# Main.net
KiCad netlist of a schematic drawn in Altium Designer
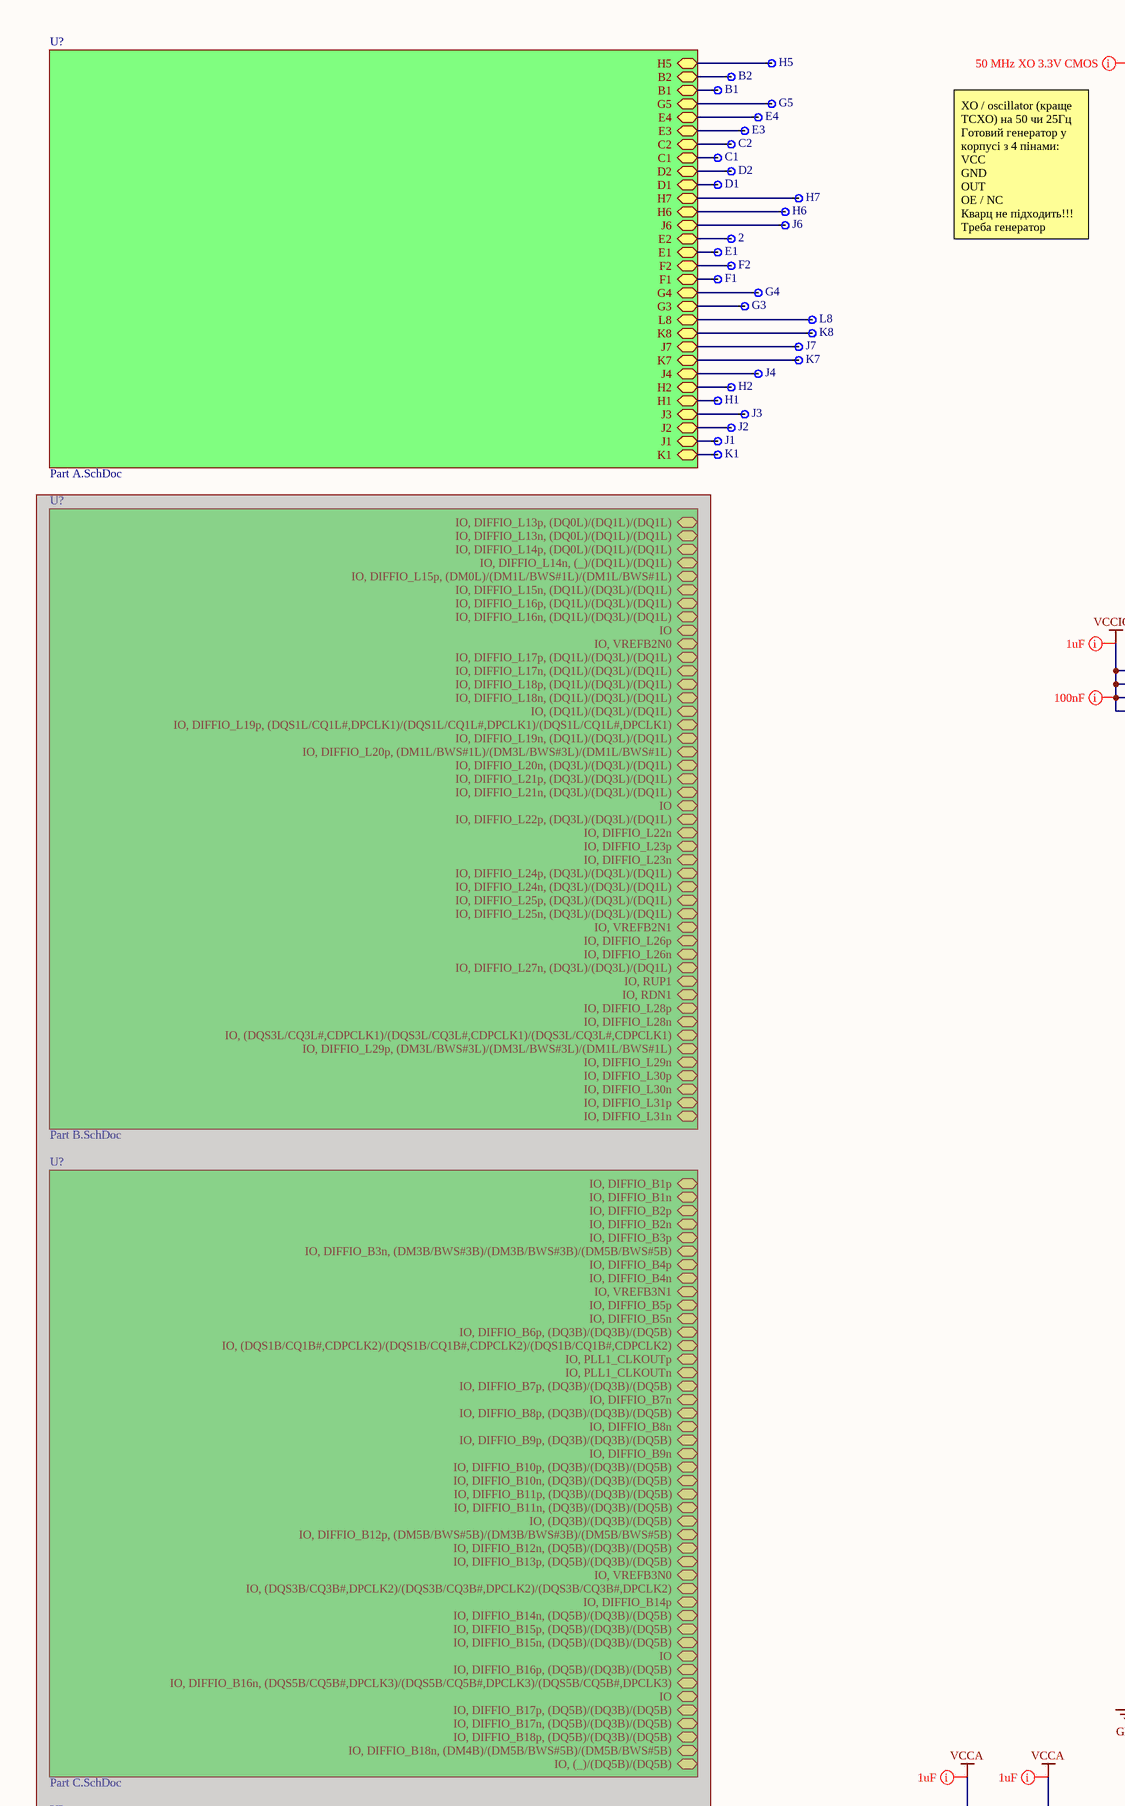
[diagram p0: Main.SchDoc, top left]
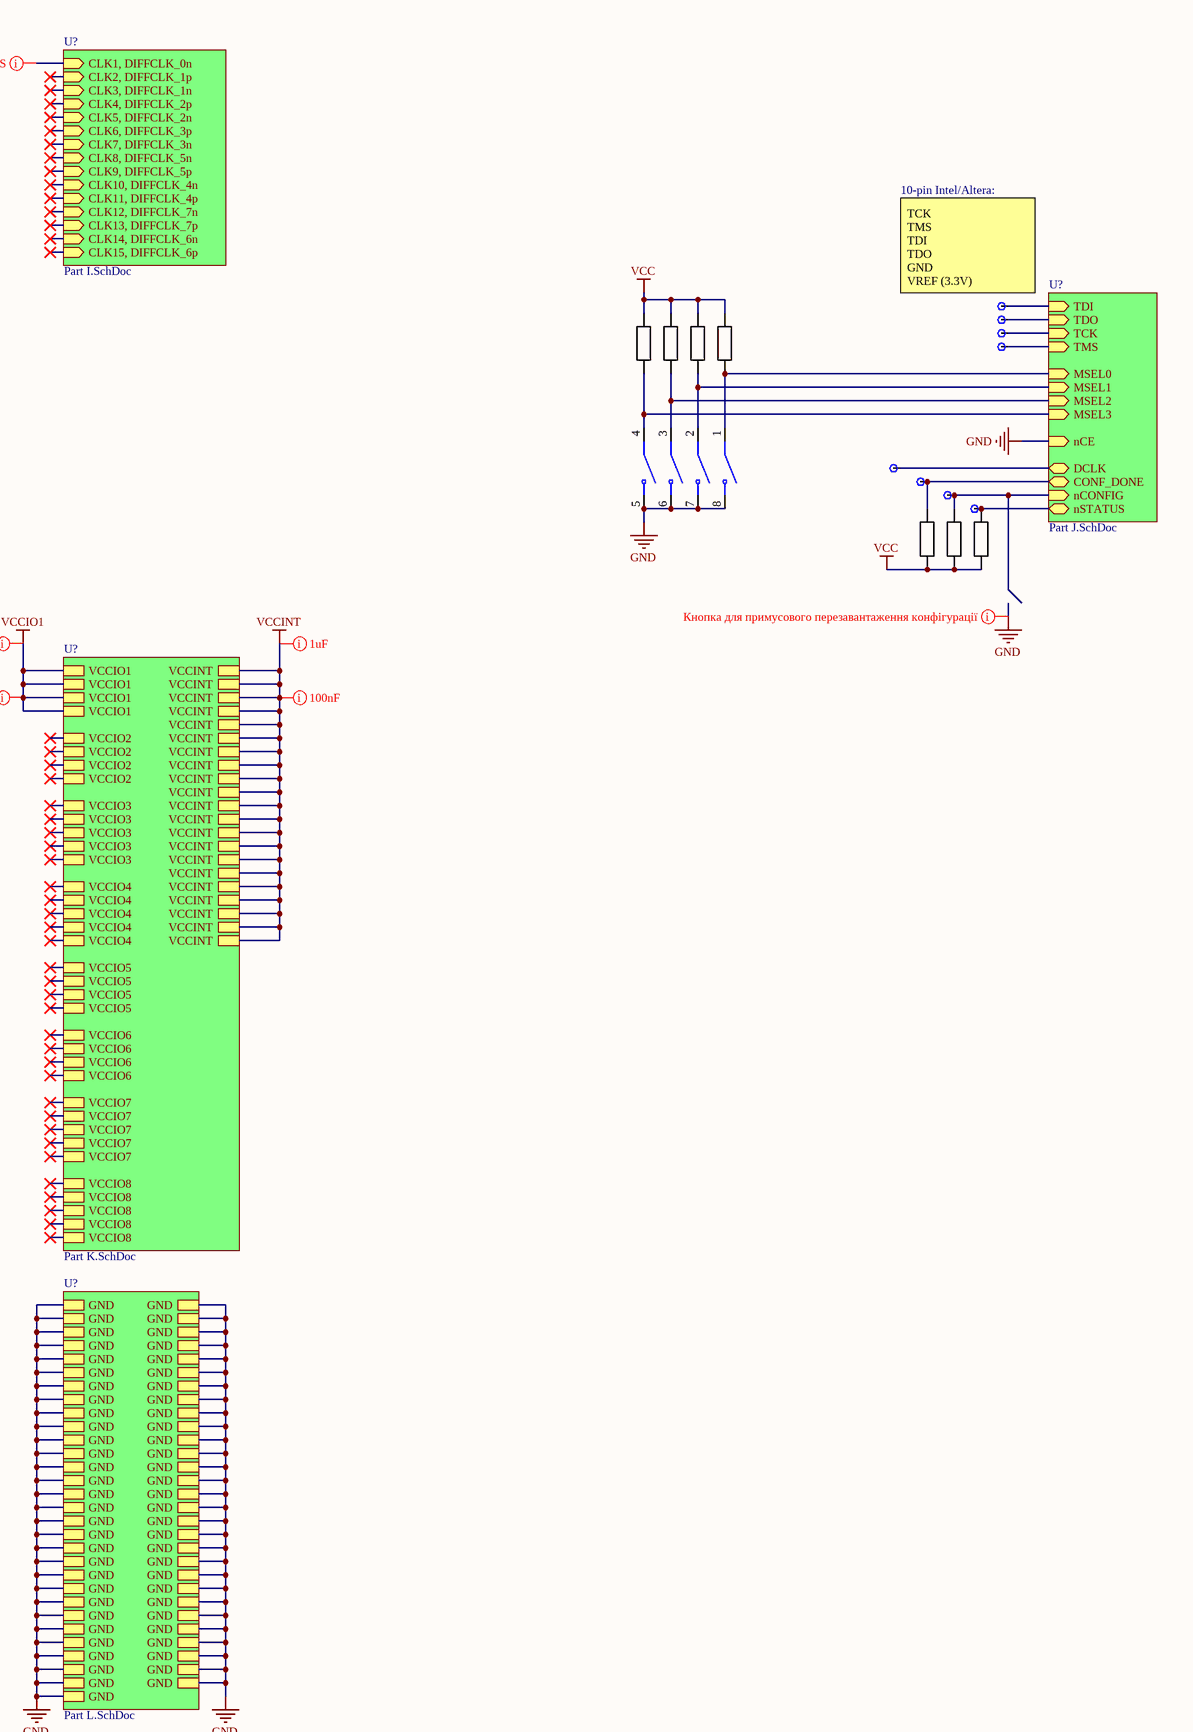
[diagram p1: Main.SchDoc, top right]
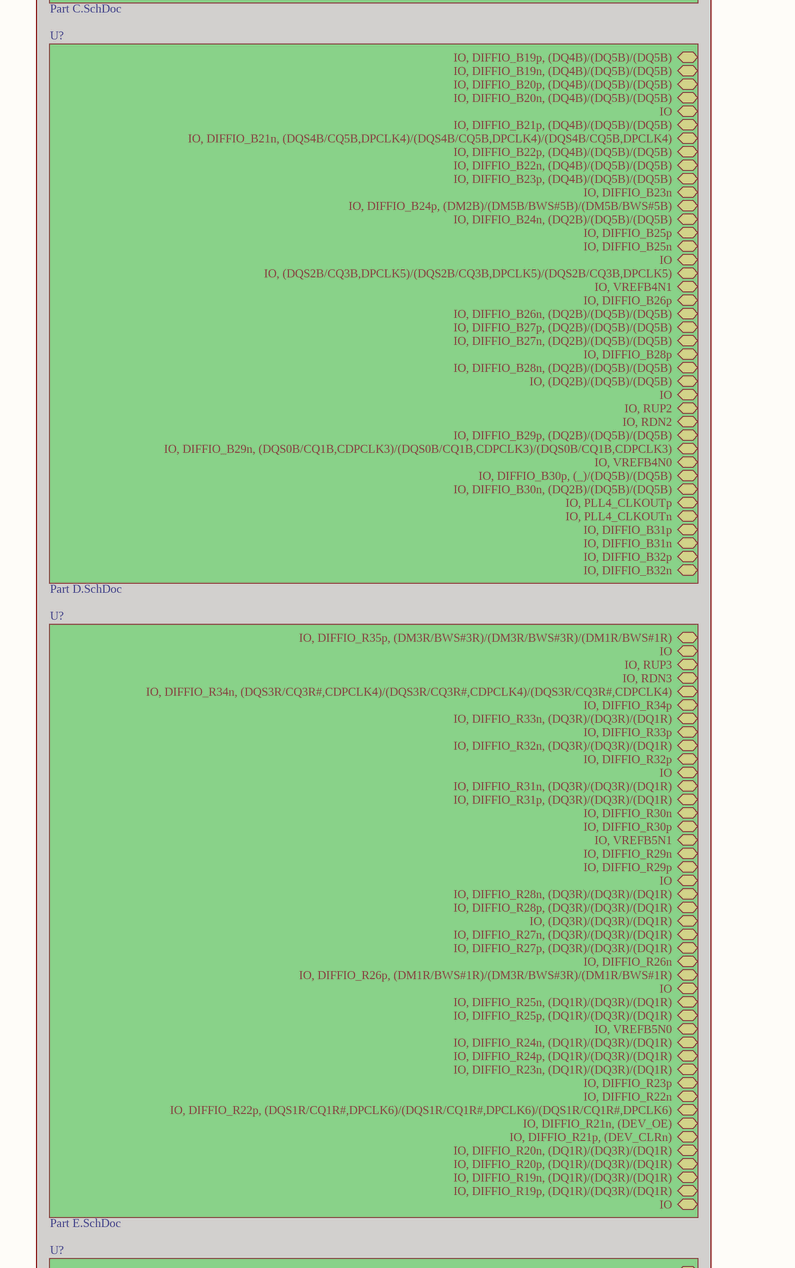
[diagram p2: Main.SchDoc, centre left]
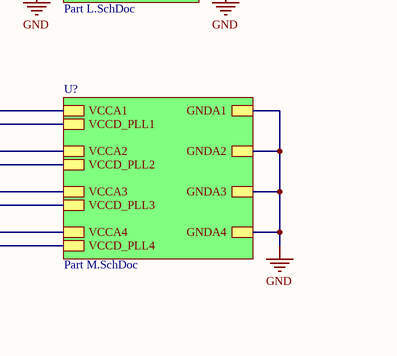
[diagram p3: Main.SchDoc, centre right]
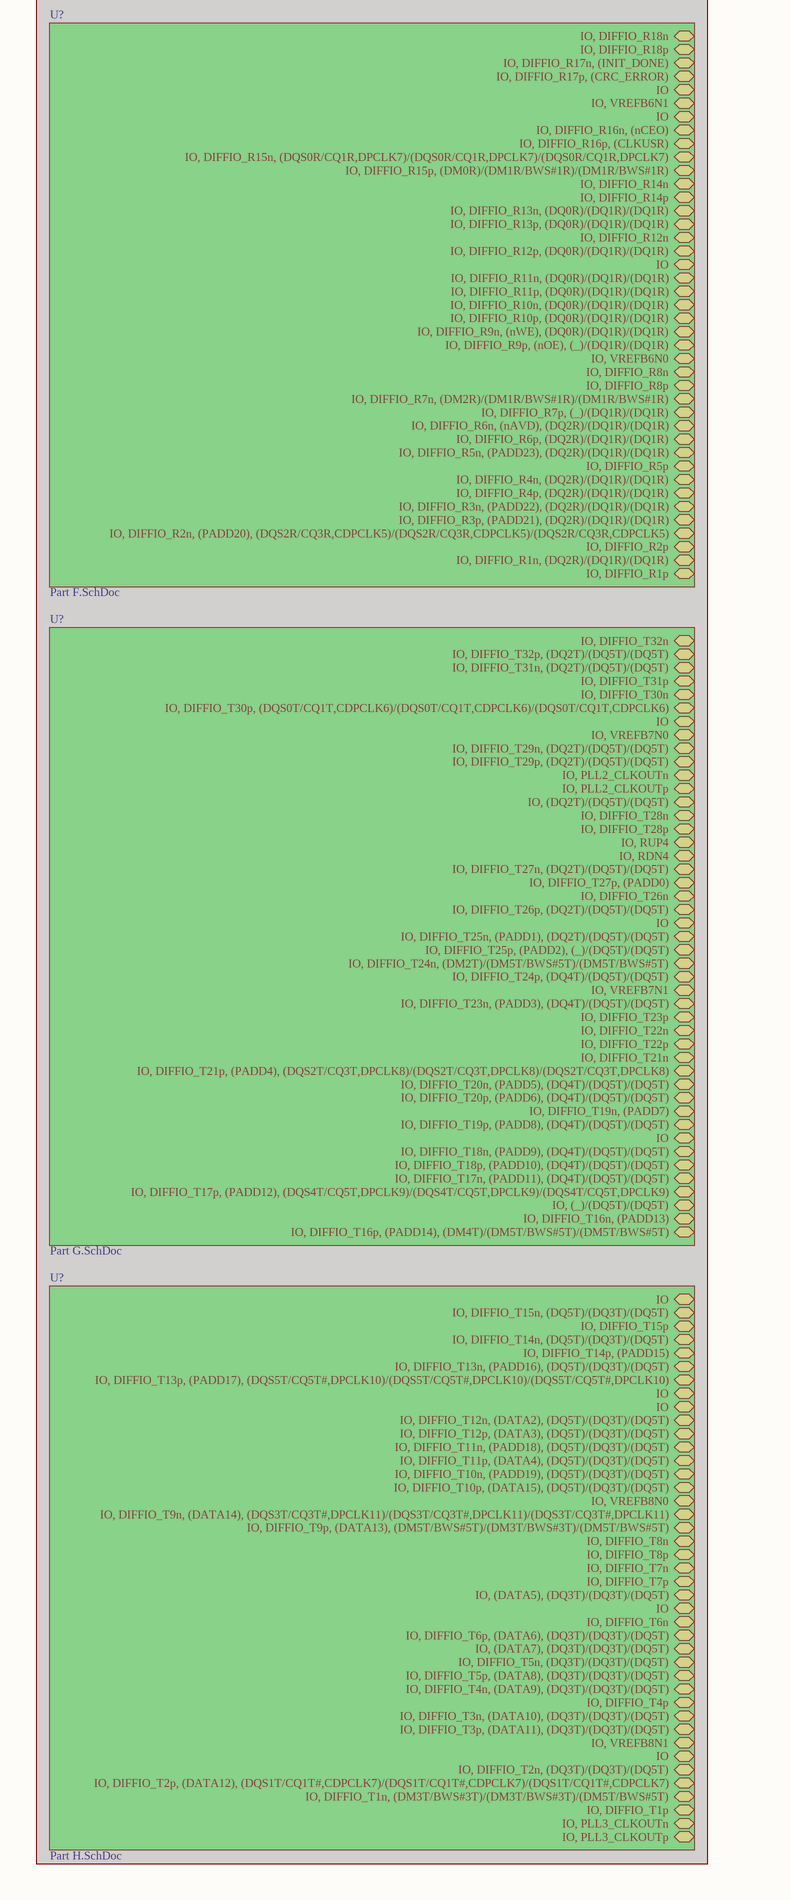
[diagram p4: Main.SchDoc, bottom left]

(export (version "E")
  (design (tool "Eeschema 10.0.6"))
  (components
    (comp (ref "J161") (value "H5") (footprint "Pin1") (libsource (lib "Schlib1") (part "Pin1")))
    (comp (ref "J162") (value "B2") (footprint "Pin1") (libsource (lib "Schlib1") (part "Pin1")))
    (comp (ref "J163") (value "B1") (footprint "Pin1") (libsource (lib "Schlib1") (part "Pin1")))
    (comp (ref "J164") (value "G5") (footprint "Pin1") (libsource (lib "Schlib1") (part "Pin1")))
    (comp (ref "J165") (value "E4") (footprint "Pin1") (libsource (lib "Schlib1") (part "Pin1")))
    (comp (ref "J166") (value "E3") (footprint "Pin1") (libsource (lib "Schlib1") (part "Pin1")))
    (comp (ref "J167") (value "C2") (footprint "Pin1") (libsource (lib "Schlib1") (part "Pin1")))
    (comp (ref "J168") (value "C1") (footprint "Pin1") (libsource (lib "Schlib1") (part "Pin1")))
    (comp (ref "J169") (value "D2") (footprint "Pin1") (libsource (lib "Schlib1") (part "Pin1")))
    (comp (ref "J170") (value "D1") (footprint "Pin1") (libsource (lib "Schlib1") (part "Pin1")))
    (comp (ref "J171") (value "H7") (footprint "Pin1") (libsource (lib "Schlib1") (part "Pin1")))
    (comp (ref "J172") (value "H6") (footprint "Pin1") (libsource (lib "Schlib1") (part "Pin1")))
    (comp (ref "J173") (value "J6") (footprint "Pin1") (libsource (lib "Schlib1") (part "Pin1")))
    (comp (ref "J174") (value "2") (footprint "Pin1") (libsource (lib "Schlib1") (part "Pin1")))
    (comp (ref "J175") (value "E1") (footprint "Pin1") (libsource (lib "Schlib1") (part "Pin1")))
    (comp (ref "J176") (value "F2") (footprint "Pin1") (libsource (lib "Schlib1") (part "Pin1")))
    (comp (ref "J177") (value "F1") (footprint "Pin1") (libsource (lib "Schlib1") (part "Pin1")))
    (comp (ref "J178") (value "G4") (footprint "Pin1") (libsource (lib "Schlib1") (part "Pin1")))
    (comp (ref "J179") (value "G3") (footprint "Pin1") (libsource (lib "Schlib1") (part "Pin1")))
    (comp (ref "J180") (value "Pin1") (footprint "Pin1") (libsource (lib "Schlib1") (part "Pin1")))
    (comp (ref "J181") (value "L8") (footprint "Pin1") (libsource (lib "Schlib1") (part "Pin1")))
    (comp (ref "J182") (value "Pin1") (footprint "Pin1") (libsource (lib "Schlib1") (part "Pin1")))
    (comp (ref "J183") (value "K8") (footprint "Pin1") (libsource (lib "Schlib1") (part "Pin1")))
    (comp (ref "J184") (value "Pin1") (footprint "Pin1") (libsource (lib "Schlib1") (part "Pin1")))
    (comp (ref "J185") (value "J7") (footprint "Pin1") (libsource (lib "Schlib1") (part "Pin1")))
    (comp (ref "J186") (value "Pin1") (footprint "Pin1") (libsource (lib "Schlib1") (part "Pin1")))
    (comp (ref "J187") (value "K7") (footprint "Pin1") (libsource (lib "Schlib1") (part "Pin1")))
    (comp (ref "J188") (value "J4") (footprint "Pin1") (libsource (lib "Schlib1") (part "Pin1")))
    (comp (ref "J189") (value "H2") (footprint "Pin1") (libsource (lib "Schlib1") (part "Pin1")))
    (comp (ref "J190") (value "H1") (footprint "Pin1") (libsource (lib "Schlib1") (part "Pin1")))
    (comp (ref "J191") (value "J3") (footprint "Pin1") (libsource (lib "Schlib1") (part "Pin1")))
    (comp (ref "J192") (value "J2") (footprint "Pin1") (libsource (lib "Schlib1") (part "Pin1")))
    (comp (ref "J193") (value "J1") (footprint "Pin1") (libsource (lib "Schlib1") (part "Pin1")))
    (comp (ref "J194") (value "K1") (footprint "Pin1") (libsource (lib "Schlib1") (part "Pin1")))
    (comp (ref "J195") (value "Pin1") (footprint "Pin1") (libsource (lib "Schlib1") (part "Pin1")))
    (comp (ref "J196") (value "Pin1") (footprint "Pin1") (libsource (lib "Schlib1") (part "Pin1")))
    (comp (ref "J197") (value "Pin1") (footprint "Pin1") (libsource (lib "Schlib1") (part "Pin1")))
    (comp (ref "J198") (value "Pin1") (footprint "Pin1") (libsource (lib "Schlib1") (part "Pin1")))
    (comp (ref "R1")
      (value "10kOm 0603")
      (footprint "RES 0603")
      (libsource (lib "Schlib1") (part "10kOm 0603"))
    )
    (comp (ref "R2")
      (value "10kOm 0603")
      (footprint "RES 0603")
      (libsource (lib "Schlib1") (part "10kOm 0603"))
    )
    (comp (ref "R3")
      (value "10kOm 0603")
      (footprint "RES 0603")
      (libsource (lib "Schlib1") (part "10kOm 0603"))
    )
    (comp (ref "R4")
      (value "10kOm 0603")
      (footprint "RES 0603")
      (libsource (lib "Schlib1") (part "10kOm 0603"))
    )
    (comp (ref "R5")
      (value "10kOm 0603")
      (footprint "RES 0603")
      (libsource (lib "Schlib1") (part "10kOm 0603"))
    )
    (comp (ref "R6")
      (value "10kOm 0603")
      (footprint "RES 0603")
      (libsource (lib "Schlib1") (part "10kOm 0603"))
    )
    (comp (ref "R7")
      (value "10kOm 0603")
      (footprint "RES 0603")
      (libsource (lib "Schlib1") (part "10kOm 0603"))
    )
    (comp (ref "S1")
      (value "206-4")
      (footprint "SW_206-4")
      (fields (field (name "MF") "{'manufacturer': u'CTS Components'}"))
      (libsource (lib "Schlib1") (part "206-4"))
    )
  )
  (nets
    (net (code "1") (name "/B1") (class "Default")
      (node (ref "J163") (pin "1") (pinfunction "1_1") (pintype "passive"))
    )
    (net (code "2") (name "/B2") (class "Default")
      (node (ref "J162") (pin "1") (pinfunction "1_1") (pintype "passive"))
    )
    (net (code "3") (name "/C1") (class "Default")
      (node (ref "J168") (pin "1") (pinfunction "1_1") (pintype "passive"))
    )
    (net (code "4") (name "/C2") (class "Default")
      (node (ref "J167") (pin "1") (pinfunction "1_1") (pintype "passive"))
    )
    (net (code "20") (name "/CONF_DONE") (class "Default")
      (node (ref "J196") (pin "1") (pinfunction "1_1") (pintype "passive"))
      (node (ref "R5") (pin "2") (pinfunction "2_2") (pintype "passive"))
    )
    (net (code "21") (name "/D1") (class "Default")
      (node (ref "J170") (pin "1") (pinfunction "1_1") (pintype "passive"))
    )
    (net (code "22") (name "/D2") (class "Default")
      (node (ref "J169") (pin "1") (pinfunction "1_1") (pintype "passive"))
    )
    (net (code "23") (name "/DCLK") (class "Default")
      (node (ref "J195") (pin "1") (pinfunction "1_1") (pintype "passive"))
    )
    (net (code "24") (name "/E1") (class "Default")
      (node (ref "J175") (pin "1") (pinfunction "1_1") (pintype "passive"))
    )
    (net (code "25") (name "/E2") (class "Default")
      (node (ref "J174") (pin "1") (pinfunction "1_1") (pintype "passive"))
    )
    (net (code "26") (name "/E3") (class "Default")
      (node (ref "J166") (pin "1") (pinfunction "1_1") (pintype "passive"))
    )
    (net (code "27") (name "/E4") (class "Default")
      (node (ref "J165") (pin "1") (pinfunction "1_1") (pintype "passive"))
    )
    (net (code "28") (name "/F1") (class "Default")
      (node (ref "J177") (pin "1") (pinfunction "1_1") (pintype "passive"))
    )
    (net (code "29") (name "/F2") (class "Default")
      (node (ref "J176") (pin "1") (pinfunction "1_1") (pintype "passive"))
    )
    (net (code "30") (name "/G3") (class "Default")
      (node (ref "J179") (pin "1") (pinfunction "1_1") (pintype "passive"))
    )
    (net (code "31") (name "/G4") (class "Default")
      (node (ref "J178") (pin "1") (pinfunction "1_1") (pintype "passive"))
    )
    (net (code "32") (name "/G5") (class "Default")
      (node (ref "J164") (pin "1") (pinfunction "1_1") (pintype "passive"))
    )
    (net (code "33") (name "/H1") (class "Default")
      (node (ref "J190") (pin "1") (pinfunction "1_1") (pintype "passive"))
    )
    (net (code "34") (name "/H2") (class "Default")
      (node (ref "J189") (pin "1") (pinfunction "1_1") (pintype "passive"))
    )
    (net (code "35") (name "/H5") (class "Default")
      (node (ref "J161") (pin "1") (pinfunction "1_1") (pintype "passive"))
    )
    (net (code "36") (name "/H6") (class "Default")
      (node (ref "J172") (pin "1") (pinfunction "1_1") (pintype "passive"))
    )
    (net (code "37") (name "/H7") (class "Default")
      (node (ref "J171") (pin "1") (pinfunction "1_1") (pintype "passive"))
    )
    (net (code "336") (name "/J1") (class "Default")
      (node (ref "J193") (pin "1") (pinfunction "1_1") (pintype "passive"))
    )
    (net (code "337") (name "/J2") (class "Default")
      (node (ref "J192") (pin "1") (pinfunction "1_1") (pintype "passive"))
    )
    (net (code "338") (name "/J3") (class "Default")
      (node (ref "J191") (pin "1") (pinfunction "1_1") (pintype "passive"))
    )
    (net (code "339") (name "/J4") (class "Default")
      (node (ref "J188") (pin "1") (pinfunction "1_1") (pintype "passive"))
    )
    (net (code "340") (name "/J6") (class "Default")
      (node (ref "J173") (pin "1") (pinfunction "1_1") (pintype "passive"))
    )
    (net (code "341") (name "/J7") (class "Default")
      (node (ref "J185") (pin "1") (pinfunction "1_1") (pintype "passive"))
    )
    (net (code "342") (name "/K1") (class "Default")
      (node (ref "J194") (pin "1") (pinfunction "1_1") (pintype "passive"))
    )
    (net (code "343") (name "/K7") (class "Default")
      (node (ref "J187") (pin "1") (pinfunction "1_1") (pintype "passive"))
    )
    (net (code "344") (name "/K8") (class "Default")
      (node (ref "J183") (pin "1") (pinfunction "1_1") (pintype "passive"))
    )
    (net (code "345") (name "/L8") (class "Default")
      (node (ref "J181") (pin "1") (pinfunction "1_1") (pintype "passive"))
    )
    (net (code "346") (name "/MSEL0") (class "Default")
      (node (ref "R4") (pin "1") (pinfunction "1_1") (pintype "passive"))
      (node (ref "S1") (pin "1") (pinfunction "COM1_1") (pintype "passive"))
    )
    (net (code "347") (name "/MSEL1") (class "Default")
      (node (ref "R3") (pin "1") (pinfunction "1_1") (pintype "passive"))
      (node (ref "S1") (pin "2") (pinfunction "COM2_2") (pintype "passive"))
    )
    (net (code "348") (name "/MSEL2") (class "Default")
      (node (ref "R2") (pin "1") (pinfunction "1_1") (pintype "passive"))
      (node (ref "S1") (pin "3") (pinfunction "COM3_3") (pintype "passive"))
    )
    (net (code "349") (name "/MSEL3") (class "Default")
      (node (ref "R1") (pin "1") (pinfunction "1_1") (pintype "passive"))
      (node (ref "S1") (pin "4") (pinfunction "COM4_4") (pintype "passive"))
    )
    (net (code "350") (name "/TCK") (class "Default")
      (node (ref "J184") (pin "1") (pinfunction "1_1") (pintype "passive"))
    )
    (net (code "351") (name "/TDI") (class "Default")
      (node (ref "J180") (pin "1") (pinfunction "1_1") (pintype "passive"))
    )
    (net (code "352") (name "/TDO") (class "Default")
      (node (ref "J182") (pin "1") (pinfunction "1_1") (pintype "passive"))
    )
    (net (code "353") (name "/TMS") (class "Default")
      (node (ref "J186") (pin "1") (pinfunction "1_1") (pintype "passive"))
    )
    (net (code "386") (name "/nCONFIG") (class "Default")
      (node (ref "J197") (pin "1") (pinfunction "1_1") (pintype "passive"))
      (node (ref "R6") (pin "2") (pinfunction "2_2") (pintype "passive"))
    )
    (net (code "387") (name "/nSTATUS") (class "Default")
      (node (ref "J198") (pin "1") (pinfunction "1_1") (pintype "passive"))
      (node (ref "R7") (pin "2") (pinfunction "2_2") (pintype "passive"))
    )
    (net (code "388") (name "GND") (class "Default")
      (node (ref "S1") (pin "5") (pinfunction "NO4_5") (pintype "passive"))
      (node (ref "S1") (pin "6") (pinfunction "NO3_6") (pintype "passive"))
      (node (ref "S1") (pin "7") (pinfunction "NO2_7") (pintype "passive"))
      (node (ref "S1") (pin "8") (pinfunction "NO1_8") (pintype "passive"))
    )
    (net (code "389") (name "VCC") (class "Default")
      (node (ref "R1") (pin "2") (pinfunction "2_2") (pintype "passive"))
      (node (ref "R2") (pin "2") (pinfunction "2_2") (pintype "passive"))
      (node (ref "R3") (pin "2") (pinfunction "2_2") (pintype "passive"))
      (node (ref "R4") (pin "2") (pinfunction "2_2") (pintype "passive"))
      (node (ref "R5") (pin "1") (pinfunction "1_1") (pintype "passive"))
      (node (ref "R6") (pin "1") (pinfunction "1_1") (pintype "passive"))
      (node (ref "R7") (pin "1") (pinfunction "1_1") (pintype "passive"))
    )
  )
)
